# PSFB_gate_driver_sch.net
KiCad netlist of a schematic drawn in Altium Designer
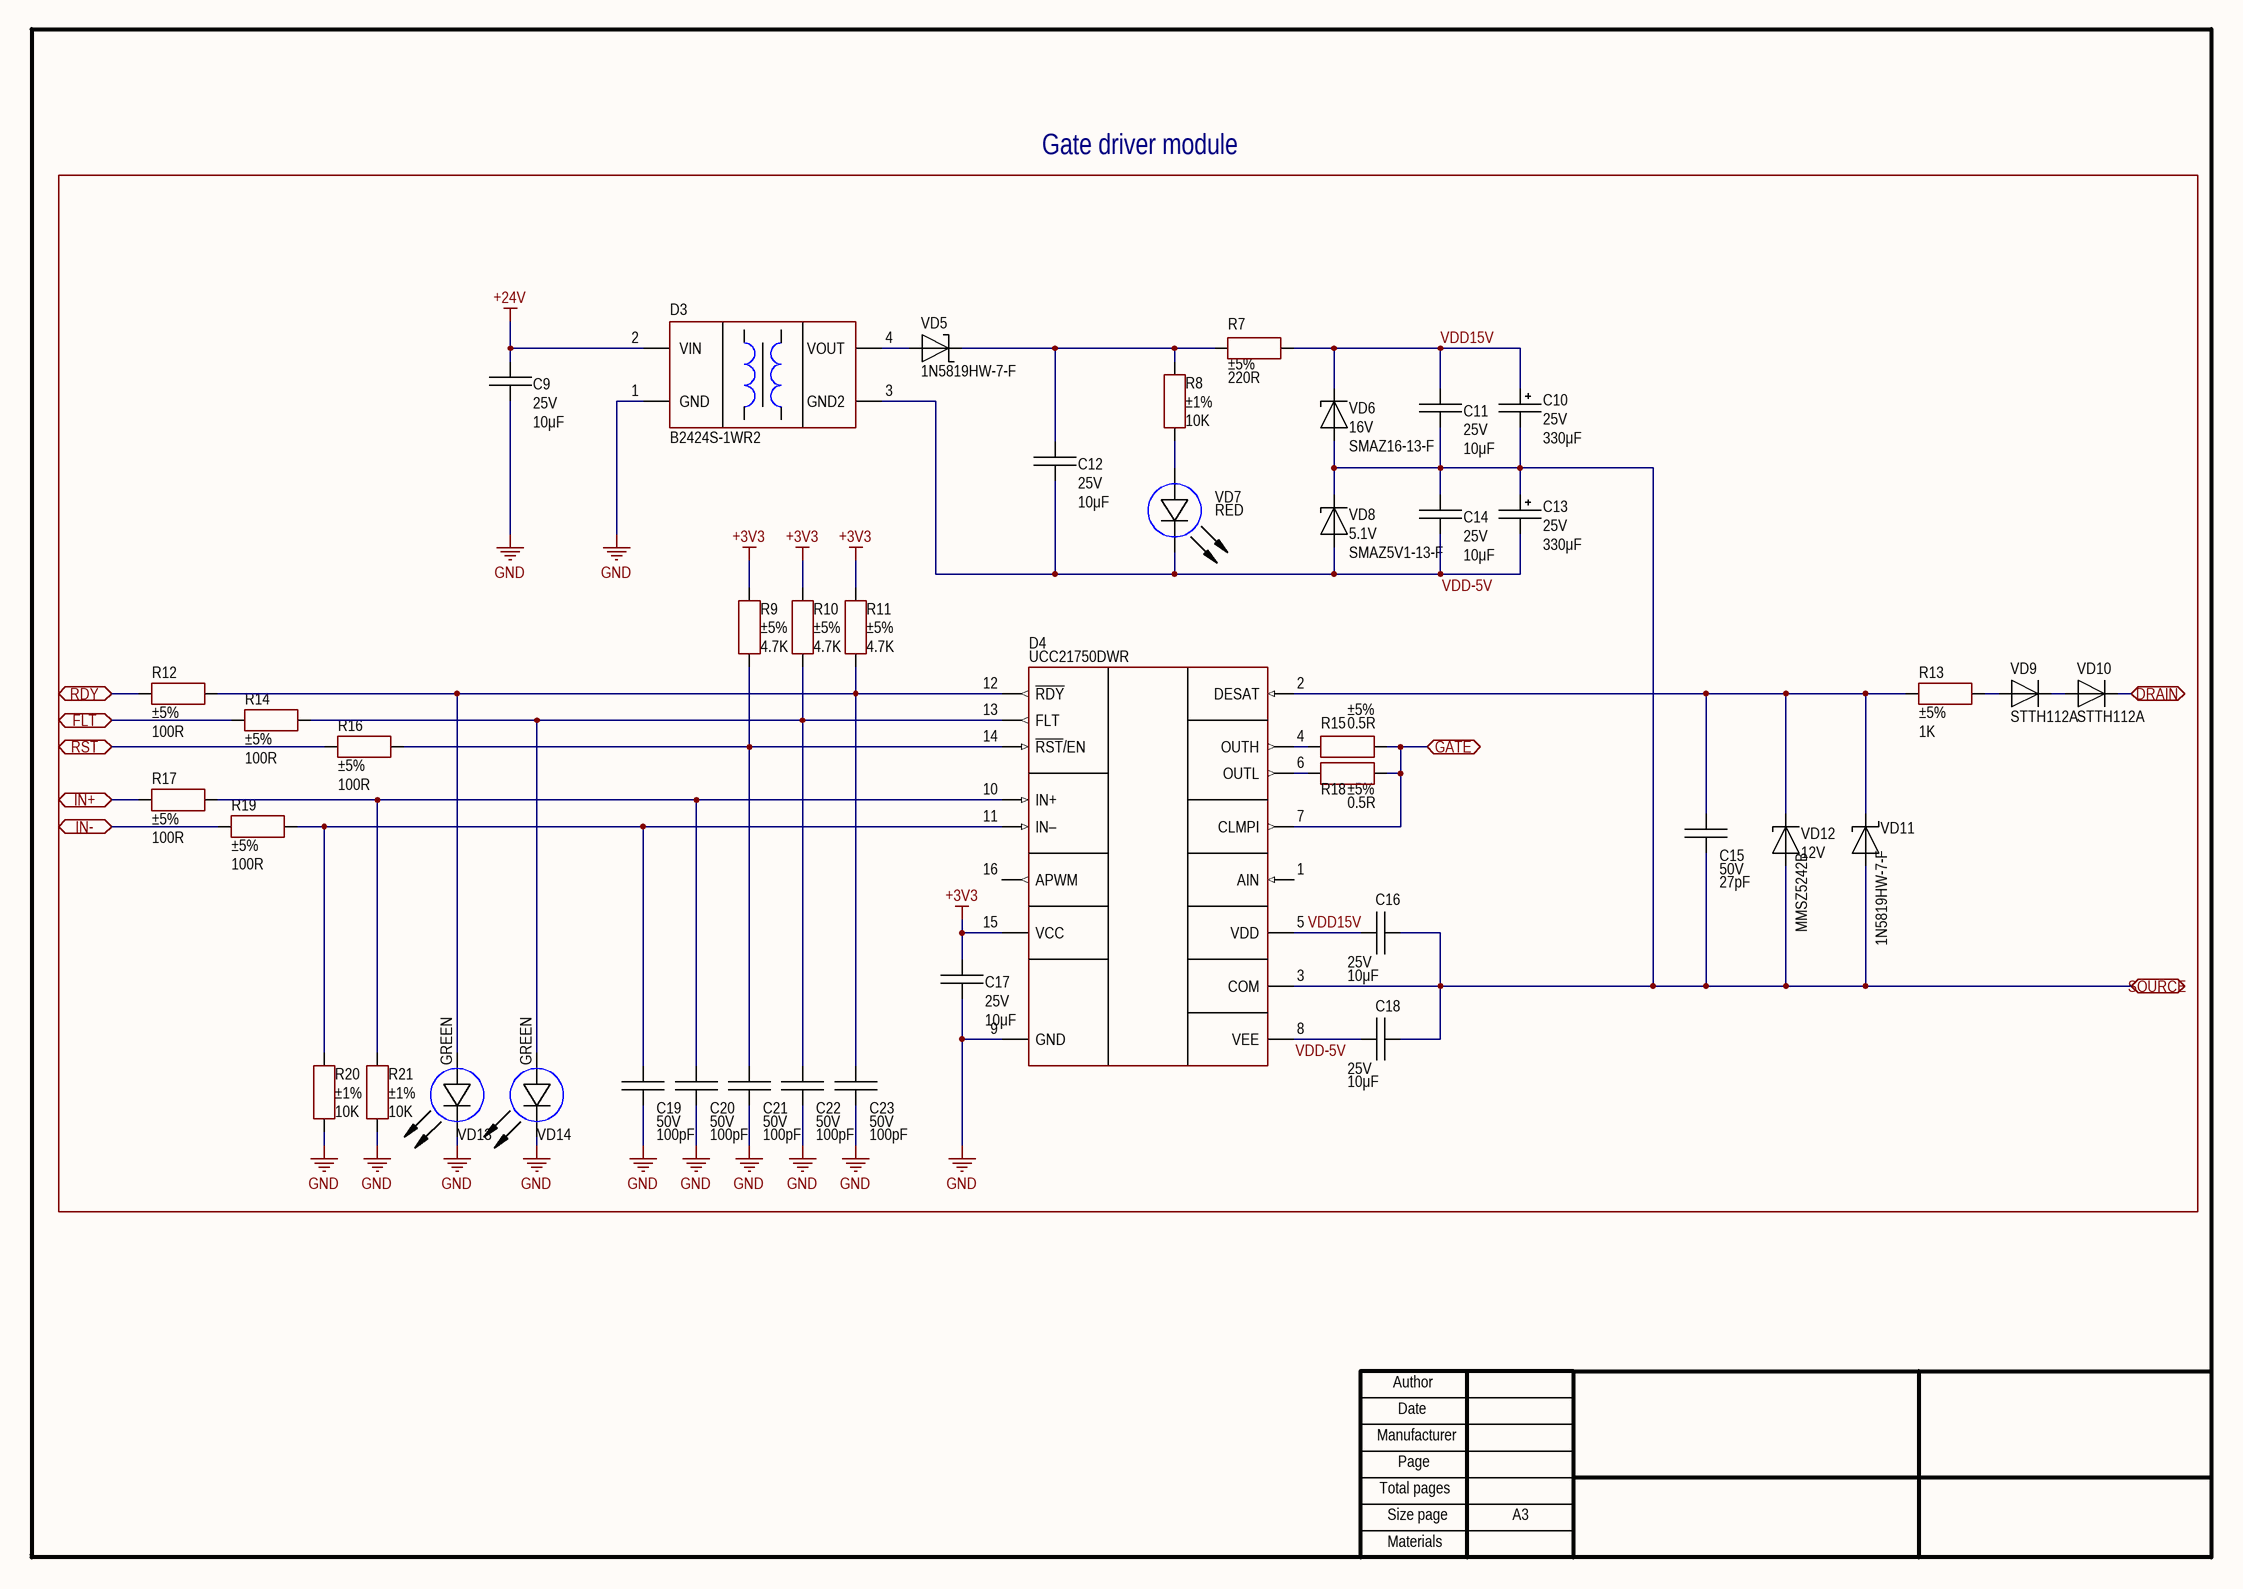
[diagram p0: PSFB_gate_driver_sch.SchDoc]

(export (version "E")
  (design (tool "Eeschema 10.0.6"))
  (components
    (comp (ref "C9")
      (value "10μF")
      (footprint "CAP: 1206")
      (description "10µF ±10% 25V Ceramic Capacitor X7R 1206 (3216 Metric)")
      (fields
        (field (name "MANUFACTURER") "Yageo")
        (field (name "PARTNUMBER") "CC1206KKX7R8BB106")
        (field (name "VOLTAGE") "25V")
      )
      (libsource (lib "capacitor") (part "Ceramic_1206"))
    )
    (comp (ref "C10")
      (value "330μF")
      (footprint "CAP: D8C3.5H12")
      (description "330µF 25V Aluminum - Polymer Capacitors Radial, Can 18mOhm 2000 Hrs @ 105°C")
      (fields
        (field (name "MANUFACTURER") "KEMET")
        (field (name "PARTNUMBER") "A750KS337M1EAAE018")
        (field (name "VOLTAGE") "25V")
      )
      (libsource (lib "capacitor") (part "Aluminium"))
    )
    (comp (ref "C11")
      (value "10μF")
      (footprint "CAP: 1206")
      (description "10µF ±10% 25V Ceramic Capacitor X7R 1206 (3216 Metric)")
      (fields
        (field (name "MANUFACTURER") "Yageo")
        (field (name "PARTNUMBER") "CC1206KKX7R8BB106")
        (field (name "VOLTAGE") "25V")
      )
      (libsource (lib "capacitor") (part "Ceramic_1206"))
    )
    (comp (ref "C12")
      (value "10μF")
      (footprint "CAP: 1206")
      (description "10µF ±10% 25V Ceramic Capacitor X7R 1206 (3216 Metric)")
      (fields
        (field (name "MANUFACTURER") "Yageo")
        (field (name "PARTNUMBER") "CC1206KKX7R8BB106")
        (field (name "VOLTAGE") "25V")
      )
      (libsource (lib "capacitor") (part "Ceramic_1206"))
    )
    (comp (ref "C13")
      (value "330μF")
      (footprint "CAP: D8C3.5H12")
      (description "330µF 25V Aluminum - Polymer Capacitors Radial, Can 18mOhm 2000 Hrs @ 105°C")
      (fields
        (field (name "MANUFACTURER") "KEMET")
        (field (name "PARTNUMBER") "A750KS337M1EAAE018")
        (field (name "VOLTAGE") "25V")
      )
      (libsource (lib "capacitor") (part "Aluminium"))
    )
    (comp (ref "C14")
      (value "10μF")
      (footprint "CAP: 1206")
      (description "10µF ±10% 25V Ceramic Capacitor X7R 1206 (3216 Metric)")
      (fields
        (field (name "MANUFACTURER") "Yageo")
        (field (name "PARTNUMBER") "CC1206KKX7R8BB106")
        (field (name "VOLTAGE") "25V")
      )
      (libsource (lib "capacitor") (part "Ceramic_1206"))
    )
    (comp (ref "C15")
      (value "27pF")
      (footprint "CAP: 0805")
      (description "27pF ±5% 50V Ceramic Capacitor C0G, NP0 0805 (2012 Metric)")
      (fields
        (field (name "MANUFACTURER") "Yageo")
        (field (name "PARTNUMBER") "CC0805JRNPO9BN270")
        (field (name "VOLTAGE") "50V")
      )
      (libsource (lib "capacitor") (part "Ceramic_0805"))
    )
    (comp (ref "C16")
      (value "10μF")
      (footprint "CAP: 1206")
      (description "10µF ±10% 25V Ceramic Capacitor X7R 1206 (3216 Metric)")
      (fields
        (field (name "MANUFACTURER") "Yageo")
        (field (name "PARTNUMBER") "CC1206KKX7R8BB106")
        (field (name "VOLTAGE") "25V")
      )
      (libsource (lib "capacitor") (part "Ceramic_1206"))
    )
    (comp (ref "C17")
      (value "10μF")
      (footprint "CAP: 1206")
      (description "10µF ±10% 25V Ceramic Capacitor X7R 1206 (3216 Metric)")
      (fields
        (field (name "MANUFACTURER") "Yageo")
        (field (name "PARTNUMBER") "CC1206KKX7R8BB106")
        (field (name "VOLTAGE") "25V")
      )
      (libsource (lib "capacitor") (part "Ceramic_1206"))
    )
    (comp (ref "C18")
      (value "10μF")
      (footprint "CAP: 1206")
      (description "10µF ±10% 25V Ceramic Capacitor X7R 1206 (3216 Metric)")
      (fields
        (field (name "MANUFACTURER") "Yageo")
        (field (name "PARTNUMBER") "CC1206KKX7R8BB106")
        (field (name "VOLTAGE") "25V")
      )
      (libsource (lib "capacitor") (part "Ceramic_1206"))
    )
    (comp (ref "C19")
      (value "100pF")
      (footprint "CAP: 0805")
      (description "100pF ±5% 50V Ceramic Capacitor C0G, NP0 0805 (2012 Metric)")
      (fields
        (field (name "MANUFACTURER") "Yageo")
        (field (name "PARTNUMBER") "CC0805JRNPO9BN101")
        (field (name "VOLTAGE") "50V")
      )
      (libsource (lib "capacitor") (part "Ceramic_0805"))
    )
    (comp (ref "C20")
      (value "100pF")
      (footprint "CAP: 0805")
      (description "100pF ±5% 50V Ceramic Capacitor C0G, NP0 0805 (2012 Metric)")
      (fields
        (field (name "MANUFACTURER") "Yageo")
        (field (name "PARTNUMBER") "CC0805JRNPO9BN101")
        (field (name "VOLTAGE") "50V")
      )
      (libsource (lib "capacitor") (part "Ceramic_0805"))
    )
    (comp (ref "C21")
      (value "100pF")
      (footprint "CAP: 0805")
      (description "100pF ±5% 50V Ceramic Capacitor C0G, NP0 0805 (2012 Metric)")
      (fields
        (field (name "MANUFACTURER") "Yageo")
        (field (name "PARTNUMBER") "CC0805JRNPO9BN101")
        (field (name "VOLTAGE") "50V")
      )
      (libsource (lib "capacitor") (part "Ceramic_0805"))
    )
    (comp (ref "C22")
      (value "100pF")
      (footprint "CAP: 0805")
      (description "100pF ±5% 50V Ceramic Capacitor C0G, NP0 0805 (2012 Metric)")
      (fields
        (field (name "MANUFACTURER") "Yageo")
        (field (name "PARTNUMBER") "CC0805JRNPO9BN101")
        (field (name "VOLTAGE") "50V")
      )
      (libsource (lib "capacitor") (part "Ceramic_0805"))
    )
    (comp (ref "C23")
      (value "100pF")
      (footprint "CAP: 0805")
      (description "100pF ±5% 50V Ceramic Capacitor C0G, NP0 0805 (2012 Metric)")
      (fields
        (field (name "MANUFACTURER") "Yageo")
        (field (name "PARTNUMBER") "CC0805JRNPO9BN101")
        (field (name "VOLTAGE") "50V")
      )
      (libsource (lib "capacitor") (part "Ceramic_0805"))
    )
    (comp (ref "D3")
      (value "~")
      (footprint "MOD: SIP-4 (B0505S-1W)")
      (description "Isolated Module DC DC Converter 1 Output 24V 42mA 21.6V - 26.4V Input")
      (fields
        (field (name "MANUFACTURER") "Mornsun")
        (field (name "VALUEMANUFACTURERPARTNUMBER") "DC/DC converter, Isolator, 24V 42mA, -40...+105°C, SIP-4")
        (field (name "PARTNUMBER") "B2424S-1WR2")
      )
      (libsource (lib "module") (part "B0505S-1WR2"))
    )
    (comp (ref "D4")
      (value "~")
      (footprint "16-SOIC")
      (description "10A Gate Driver Capacitive Coupling 5700Vrms 1 Channel 16-SOIC")
      (fields
        (field (name "MANUFACTURER") "Texas Instruments")
        (field (name "VALUEMANUFACTURERPARTNUMBER") "Isolated gate driver, 1200V, , ±10A, 150kV/μs, supply 3...5.5V, -40...+125°C, 16-SOIC")
        (field (name "PARTNUMBER") "UCC21750DWR")
      )
      (libsource (lib "MyLib") (part "UCC21750DWR"))
    )
    (comp (ref "R7")
      (value "220R")
      (footprint "RES: 2512")
      (description "220 Ohms ±5% 1W Chip Resistor 2512 (6432 Metric) Moisture Resistant Thick Film")
      (fields
        (field (name "MANUFACTURER") "Yageo")
        (field (name "PARTNUMBER") "RC2512JK-07220RL")
        (field (name "TOLERANCE") "±5%")
      )
      (libsource (lib "resistor") (part "Resistor_2512"))
    )
    (comp (ref "R8")
      (value "10K")
      (footprint "RES: 0805")
      (description "10 kOhms ±1% 0.125W, 1/8W Chip Resistor 0805 (2012 Metric) Moisture Resistant Thick Film")
      (fields
        (field (name "MANUFACTURER") "Yageo")
        (field (name "PARTNUMBER") "RC0805FR-0710KL")
        (field (name "TOLERANCE") "±1%")
      )
      (libsource (lib "resistor") (part "Resistor_0805"))
    )
    (comp (ref "R9")
      (value "4.7K")
      (footprint "RES: 0805")
      (description "4.7 kOhms ±5% 0.125W, 1/8W Chip Resistor 0805 (2012 Metric) Moisture Resistant Thick Film")
      (fields
        (field (name "MANUFACTURER") "Yageo")
        (field (name "PARTNUMBER") "RC0805JR-074K7L")
        (field (name "TOLERANCE") "±5%")
      )
      (libsource (lib "resistor") (part "Resistor_0805"))
    )
    (comp (ref "R10")
      (value "4.7K")
      (footprint "RES: 0805")
      (description "4.7 kOhms ±5% 0.125W, 1/8W Chip Resistor 0805 (2012 Metric) Moisture Resistant Thick Film")
      (fields
        (field (name "MANUFACTURER") "Yageo")
        (field (name "PARTNUMBER") "RC0805JR-074K7L")
        (field (name "TOLERANCE") "±5%")
      )
      (libsource (lib "resistor") (part "Resistor_0805"))
    )
    (comp (ref "R11")
      (value "4.7K")
      (footprint "RES: 0805")
      (description "4.7 kOhms ±5% 0.125W, 1/8W Chip Resistor 0805 (2012 Metric) Moisture Resistant Thick Film")
      (fields
        (field (name "MANUFACTURER") "Yageo")
        (field (name "PARTNUMBER") "RC0805JR-074K7L")
        (field (name "TOLERANCE") "±5%")
      )
      (libsource (lib "resistor") (part "Resistor_0805"))
    )
    (comp (ref "R12")
      (value "100R")
      (footprint "RES: 0805")
      (description "100 Ohms ±5% 0.125W, 1/8W Chip Resistor 0805 (2012 Metric) Moisture Resistant Thick Film")
      (fields
        (field (name "MANUFACTURER") "Yageo")
        (field (name "PARTNUMBER") "RC0805JR-07100RL")
        (field (name "TOLERANCE") "±5%")
      )
      (libsource (lib "") (part "Resistor_0805_1"))
    )
    (comp (ref "R13")
      (value "1K")
      (footprint "RES: 0805")
      (description "1 kOhms ±5% 0.125W, 1/8W Chip Resistor 0805 (2012 Metric) Moisture Resistant Thick Film")
      (fields
        (field (name "MANUFACTURER") "Yageo")
        (field (name "PARTNUMBER") "RC0805JR-071KL")
        (field (name "TOLERANCE") "±5%")
      )
      (libsource (lib "") (part "Resistor_0805_1"))
    )
    (comp (ref "R14")
      (value "100R")
      (footprint "RES: 0805")
      (description "100 Ohms ±5% 0.125W, 1/8W Chip Resistor 0805 (2012 Metric) Moisture Resistant Thick Film")
      (fields
        (field (name "MANUFACTURER") "Yageo")
        (field (name "PARTNUMBER") "RC0805JR-07100RL")
        (field (name "TOLERANCE") "±5%")
      )
      (libsource (lib "") (part "Resistor_0805_1"))
    )
    (comp (ref "R15")
      (value "0.5R")
      (footprint "RES: 2512")
      (fields
        (field (name "MANUFACTURER") "Yageo")
        (field (name "PARTNUMBER") "RC2512JK-07100RL")
        (field (name "VALUEMANUFACTURERPARTNUMBER") "Resistor film, 0.5R, ±5%, 2512, 1W, -55...+125°C")
        (field (name "TOLERANCE") "±5%")
      )
      (libsource (lib "resistor") (part "Resistor_2512"))
    )
    (comp (ref "R16")
      (value "100R")
      (footprint "RES: 0805")
      (description "100 Ohms ±5% 0.125W, 1/8W Chip Resistor 0805 (2012 Metric) Moisture Resistant Thick Film")
      (fields
        (field (name "MANUFACTURER") "Yageo")
        (field (name "PARTNUMBER") "RC0805JR-07100RL")
        (field (name "TOLERANCE") "±5%")
      )
      (libsource (lib "") (part "Resistor_0805_1"))
    )
    (comp (ref "R17")
      (value "100R")
      (footprint "RES: 0805")
      (description "100 Ohms ±5% 0.125W, 1/8W Chip Resistor 0805 (2012 Metric) Moisture Resistant Thick Film")
      (fields
        (field (name "MANUFACTURER") "Yageo")
        (field (name "PARTNUMBER") "RC0805JR-07100RL")
        (field (name "TOLERANCE") "±5%")
      )
      (libsource (lib "") (part "Resistor_0805_1"))
    )
    (comp (ref "R18")
      (value "0.5R")
      (footprint "RES: 2512")
      (fields
        (field (name "MANUFACTURER") "Yageo")
        (field (name "PARTNUMBER") "RC2512JK-07100RL")
        (field (name "VALUEMANUFACTURERPARTNUMBER") "Resistor film, 0.5R, ±5%, 2512, 1W, -55...+125°C")
        (field (name "TOLERANCE") "±5%")
      )
      (libsource (lib "resistor") (part "Resistor_2512"))
    )
    (comp (ref "R19")
      (value "100R")
      (footprint "RES: 0805")
      (description "100 Ohms ±5% 0.125W, 1/8W Chip Resistor 0805 (2012 Metric) Moisture Resistant Thick Film")
      (fields
        (field (name "MANUFACTURER") "Yageo")
        (field (name "PARTNUMBER") "RC0805JR-07100RL")
        (field (name "TOLERANCE") "±5%")
      )
      (libsource (lib "") (part "Resistor_0805_1"))
    )
    (comp (ref "R20")
      (value "10K")
      (footprint "RES: 0805")
      (description "10 kOhms ±1% 0.125W, 1/8W Chip Resistor 0805 (2012 Metric) Moisture Resistant Thick Film")
      (fields
        (field (name "MANUFACTURER") "Yageo")
        (field (name "PARTNUMBER") "RC0805FR-0710KL")
        (field (name "TOLERANCE") "±1%")
      )
      (libsource (lib "") (part "Resistor_0805_2"))
    )
    (comp (ref "R21")
      (value "10K")
      (footprint "RES: 0805")
      (description "10 kOhms ±1% 0.125W, 1/8W Chip Resistor 0805 (2012 Metric) Moisture Resistant Thick Film")
      (fields
        (field (name "MANUFACTURER") "Yageo")
        (field (name "PARTNUMBER") "RC0805FR-0710KL")
        (field (name "TOLERANCE") "±1%")
      )
      (libsource (lib "") (part "Resistor_0805_2"))
    )
    (comp (ref "VD5")
      (value "~")
      (footprint "DIODE: SOD123")
      (description "Diode Schottky 40V 1A Surface Mount SOD-123C")
      (fields
        (field (name "MANUFACTURER") "Diodes Incorporated")
        (field (name "VALUEMANUFACTURERPARTNUMBER") "Schottky diode, 40V, 1A, 0.45V, 15pF, SOD-123, -55...+150°C")
        (field (name "PARTNUMBER") "1N5819HW-7-F")
      )
      (libsource (lib "diode") (part "Schottky_single"))
    )
    (comp (ref "VD6")
      (value "~")
      (footprint "DIODE: SMA")
      (description "Zener Diode 16V 1W ±5% Surface Mount SMA")
      (fields
        (field (name "MANUFACTURER") "Diodes Incorporated")
        (field (name "VALUEMANUFACTURERPARTNUMBER") "Zener diode, 16V, 1W, 0.9V, 17Ohm, SMA, -55...+150°C")
        (field (name "VOLTAGE") "16V")
        (field (name "PARTNUMBER") "SMAZ16-13-F")
      )
      (libsource (lib "diode") (part "Zener_single"))
    )
    (comp (ref "VD7")
      (value "~")
      (footprint "LED: 0805R")
      (description "Red 631nm LED Indication - Discrete 2V 0805 (2012 Metric)")
      (fields
        (field (name "MANUFACTURER") "Lite-On Inc.")
        (field (name "VALUEMANUFACTURERPARTNUMBER") "LED, Red, 20mA, 2V, 0805, -55...+150°C")
        (field (name "COLOR") "RED")
      )
      (libsource (lib "diode") (part "LED_single"))
    )
    (comp (ref "VD8")
      (value "~")
      (footprint "DIODE: SMA")
      (description "Zener Diode 5.1V 1W ±5% Surface Mount SMA")
      (fields
        (field (name "MANUFACTURER") "Diodes Incorporated")
        (field (name "VALUEMANUFACTURERPARTNUMBER") "Zener diode, 5.1V, 1W, 0.9V, 17Ohm, SMA, -55...+150°C")
        (field (name "VOLTAGE") "5.1V")
        (field (name "PARTNUMBER") "SMAZ5V1-13-F")
      )
      (libsource (lib "diode") (part "Zener_single"))
    )
    (comp (ref "VD9")
      (value "~")
      (footprint "DIODE: SMA")
      (description "Diode Standard 1200V 1A Surface Mount SMA")
      (fields
        (field (name "MANUFACTURER") "STMicroelectronics")
        (field (name "VALUEMANUFACTURERPARTNUMBER") "Single diode, 1200V, 1A, 1.9V, 75ns, SMA, -55...+150°C")
        (field (name "PARTNUMBER") "STTH112A")
      )
      (libsource (lib "diode") (part "Diode_single"))
    )
    (comp (ref "VD10")
      (value "~")
      (footprint "DIODE: SMA")
      (description "Diode Standard 1200V 1A Surface Mount SMA")
      (fields
        (field (name "MANUFACTURER") "STMicroelectronics")
        (field (name "VALUEMANUFACTURERPARTNUMBER") "Single diode, 1200V, 1A, 1.9V, 75ns, SMA, -55...+150°C")
        (field (name "PARTNUMBER") "STTH112A")
      )
      (libsource (lib "diode") (part "Diode_single"))
    )
    (comp (ref "VD11")
      (value "~")
      (footprint "DIODE: SOD123")
      (description "Diode Schottky 40V 1A Surface Mount SOD-123C")
      (fields
        (field (name "MANUFACTURER") "Diodes Incorporated")
        (field (name "VALUEMANUFACTURERPARTNUMBER") "Schottky diode, 40V, 1A, 0.45V, 15pF, SOD-123, -55...+150°C")
        (field (name "PARTNUMBER") "1N5819HW-7-F")
      )
      (libsource (lib "diode") (part "Schottky_single"))
    )
    (comp (ref "VD12")
      (value "~")
      (footprint "DIODE: SOD123")
      (description "Zener Diode 12V 500mW ±5% Surface Mount SOD-123")
      (fields
        (field (name "MANUFACTURER") "Diodes Incorporated")
        (field (name "VALUEMANUFACTURERPARTNUMBER") "Zener diode, 12V, 500mW, 0.9V, 17Ohm, SOD-123, -55...+150°C")
        (field (name "VOLTAGE") "12V")
        (field (name "PARTNUMBER") "MMSZ5242B")
      )
      (libsource (lib "diode") (part "Zener_single"))
    )
    (comp (ref "VD13")
      (value "~")
      (footprint "LED: 0805G")
      (description "Green 571nm LED Indication - Discrete 2V 0805 (2012 Metric)")
      (fields
        (field (name "MANUFACTURER") "Lite-On Inc.")
        (field (name "VALUEMANUFACTURERPARTNUMBER") "LED, Green, 20mA, 2V, 0805, -55...+150°C")
        (field (name "COLOR") "GREEN")
      )
      (libsource (lib "diode") (part "LED_single"))
    )
    (comp (ref "VD14")
      (value "~")
      (footprint "LED: 0805G")
      (description "Green 571nm LED Indication - Discrete 2V 0805 (2012 Metric)")
      (fields
        (field (name "MANUFACTURER") "Lite-On Inc.")
        (field (name "VALUEMANUFACTURERPARTNUMBER") "LED, Green, 20mA, 2V, 0805, -55...+150°C")
        (field (name "COLOR") "GREEN")
      )
      (libsource (lib "diode") (part "LED_single"))
    )
  )
  (nets
    (net (code "1") (name "+3V3") (class "Default")
      (node (ref "C17") (pin "2") (pinfunction "2_2") (pintype "passive"))
      (node (ref "D4") (pin "15") (pinfunction "VCC_15") (pintype "power_in"))
      (node (ref "R10") (pin "2") (pinfunction "2_2") (pintype "passive"))
      (node (ref "R11") (pin "2") (pinfunction "2_2") (pintype "passive"))
      (node (ref "R9") (pin "2") (pinfunction "2_2") (pintype "passive"))
    )
    (net (code "2") (name "+24V") (class "Default")
      (node (ref "C9") (pin "2") (pinfunction "2_2") (pintype "passive"))
      (node (ref "D3") (pin "2") (pinfunction "VIN_2") (pintype "power_in"))
    )
    (net (code "3") (name "/DRAIN") (class "Default")
      (node (ref "VD10") (pin "2") (pinfunction "2_2") (pintype "passive"))
    )
    (net (code "4") (name "/FLT") (class "Default")
      (node (ref "R14") (pin "1") (pinfunction "1_1") (pintype "passive"))
    )
    (net (code "5") (name "/GATE") (class "Default")
      (node (ref "D4") (pin "7") (pinfunction "CLMPI_7") (pintype "output"))
      (node (ref "R15") (pin "2") (pinfunction "2_2") (pintype "passive"))
      (node (ref "R18") (pin "2") (pinfunction "2_2") (pintype "passive"))
    )
    (net (code "6") (name "/IN+") (class "Default")
      (node (ref "R17") (pin "1") (pinfunction "1_1") (pintype "passive"))
    )
    (net (code "7") (name "/IN-") (class "Default")
      (node (ref "R19") (pin "1") (pinfunction "1_1") (pintype "passive"))
    )
    (net (code "8") (name "/RDY") (class "Default")
      (node (ref "R12") (pin "1") (pinfunction "1_1") (pintype "passive"))
    )
    (net (code "9") (name "/RST") (class "Default")
      (node (ref "R16") (pin "1") (pinfunction "1_1") (pintype "passive"))
    )
    (net (code "10") (name "/SOURCE") (class "Default")
      (node (ref "C10") (pin "2") (pinfunction "2_2") (pintype "passive"))
      (node (ref "C11") (pin "2") (pinfunction "2_2") (pintype "passive"))
      (node (ref "C13") (pin "1") (pinfunction "1_1") (pintype "passive"))
      (node (ref "C14") (pin "1") (pinfunction "1_1") (pintype "passive"))
      (node (ref "C15") (pin "1") (pinfunction "1_1") (pintype "passive"))
      (node (ref "C16") (pin "1") (pinfunction "1_1") (pintype "passive"))
      (node (ref "C18") (pin "1") (pinfunction "1_1") (pintype "passive"))
      (node (ref "D4") (pin "3") (pinfunction "COM_3") (pintype "power_in"))
      (node (ref "VD11") (pin "1") (pinfunction "1_1") (pintype "passive"))
      (node (ref "VD12") (pin "1") (pinfunction "A_1") (pintype "passive"))
      (node (ref "VD6") (pin "1") (pinfunction "A_1") (pintype "passive"))
      (node (ref "VD8") (pin "2") (pinfunction "C_2") (pintype "passive"))
    )
    (net (code "11") (name "/VDD-5V") (class "Default")
      (node (ref "C12") (pin "1") (pinfunction "1_1") (pintype "passive"))
      (node (ref "C13") (pin "2") (pinfunction "2_2") (pintype "passive"))
      (node (ref "C14") (pin "2") (pinfunction "2_2") (pintype "passive"))
      (node (ref "C18") (pin "2") (pinfunction "2_2") (pintype "passive"))
      (node (ref "D3") (pin "3") (pinfunction "GND2_3") (pintype "power_in"))
      (node (ref "D4") (pin "8") (pinfunction "VEE_8") (pintype "power_in"))
      (node (ref "VD7") (pin "2") (pinfunction "C_2") (pintype "passive"))
      (node (ref "VD8") (pin "1") (pinfunction "A_1") (pintype "passive"))
    )
    (net (code "12") (name "/VDD15V") (class "Default")
      (node (ref "C10") (pin "1") (pinfunction "1_1") (pintype "passive"))
      (node (ref "C11") (pin "1") (pinfunction "1_1") (pintype "passive"))
      (node (ref "C16") (pin "2") (pinfunction "2_2") (pintype "passive"))
      (node (ref "D4") (pin "5") (pinfunction "VDD_5") (pintype "power_in"))
      (node (ref "R7") (pin "2") (pinfunction "2_2") (pintype "passive"))
      (node (ref "VD6") (pin "2") (pinfunction "C_2") (pintype "passive"))
    )
    (net (code "13") (name "GND") (class "Default")
      (node (ref "C17") (pin "1") (pinfunction "1_1") (pintype "passive"))
      (node (ref "C19") (pin "1") (pinfunction "1_1") (pintype "passive"))
      (node (ref "C20") (pin "1") (pinfunction "1_1") (pintype "passive"))
      (node (ref "C21") (pin "1") (pinfunction "1_1") (pintype "passive"))
      (node (ref "C22") (pin "1") (pinfunction "1_1") (pintype "passive"))
      (node (ref "C23") (pin "1") (pinfunction "1_1") (pintype "passive"))
      (node (ref "C9") (pin "1") (pinfunction "1_1") (pintype "passive"))
      (node (ref "D3") (pin "1") (pinfunction "GND_1") (pintype "power_in"))
      (node (ref "D4") (pin "9") (pinfunction "GND_9") (pintype "power_in"))
      (node (ref "R20") (pin "2") (pinfunction "2_2") (pintype "passive"))
      (node (ref "R21") (pin "2") (pinfunction "2_2") (pintype "passive"))
      (node (ref "VD13") (pin "2") (pinfunction "C_2") (pintype "passive"))
      (node (ref "VD14") (pin "2") (pinfunction "C_2") (pintype "passive"))
    )
    (net (code "14") (name "Net-(C12-Pad2)") (class "Default")
      (node (ref "C12") (pin "2") (pinfunction "2_2") (pintype "passive"))
      (node (ref "R7") (pin "1") (pinfunction "1_1") (pintype "passive"))
      (node (ref "R8") (pin "2") (pinfunction "2_2") (pintype "passive"))
      (node (ref "VD5") (pin "2") (pinfunction "2_2") (pintype "passive"))
    )
    (net (code "15") (name "Net-(D3-VOUT)") (class "Default")
      (node (ref "D3") (pin "4") (pinfunction "VOUT_4") (pintype "power_in"))
      (node (ref "VD5") (pin "1") (pinfunction "1_1") (pintype "passive"))
    )
    (net (code "16") (name "Net-(D4-DESAT)") (class "Default")
      (node (ref "C15") (pin "2") (pinfunction "2_2") (pintype "passive"))
      (node (ref "D4") (pin "2") (pinfunction "DESAT_2") (pintype "input"))
      (node (ref "R13") (pin "1") (pinfunction "1_1") (pintype "passive"))
      (node (ref "VD11") (pin "2") (pinfunction "2_2") (pintype "passive"))
      (node (ref "VD12") (pin "2") (pinfunction "C_2") (pintype "passive"))
    )
    (net (code "17") (name "Net-(D4-FLT)") (class "Default")
      (node (ref "C22") (pin "2") (pinfunction "2_2") (pintype "passive"))
      (node (ref "D4") (pin "13") (pinfunction "FLT_13") (pintype "output"))
      (node (ref "R10") (pin "1") (pinfunction "1_1") (pintype "passive"))
      (node (ref "R14") (pin "2") (pinfunction "2_2") (pintype "passive"))
      (node (ref "VD14") (pin "1") (pinfunction "A_1") (pintype "passive"))
    )
    (net (code "18") (name "Net-(D4-IN+)") (class "Default")
      (node (ref "C20") (pin "2") (pinfunction "2_2") (pintype "passive"))
      (node (ref "D4") (pin "10") (pinfunction "IN+_10") (pintype "input"))
      (node (ref "R17") (pin "2") (pinfunction "2_2") (pintype "passive"))
      (node (ref "R21") (pin "1") (pinfunction "1_1") (pintype "passive"))
    )
    (net (code "19") (name "Net-(D4-IN–)") (class "Default")
      (node (ref "C19") (pin "2") (pinfunction "2_2") (pintype "passive"))
      (node (ref "D4") (pin "11") (pinfunction "IN–_11") (pintype "input"))
      (node (ref "R19") (pin "2") (pinfunction "2_2") (pintype "passive"))
      (node (ref "R20") (pin "1") (pinfunction "1_1") (pintype "passive"))
    )
    (net (code "20") (name "Net-(D4-OUTH)") (class "Default")
      (node (ref "D4") (pin "4") (pinfunction "OUTH_4") (pintype "output"))
      (node (ref "R15") (pin "1") (pinfunction "1_1") (pintype "passive"))
    )
    (net (code "21") (name "Net-(D4-OUTL)") (class "Default")
      (node (ref "D4") (pin "6") (pinfunction "OUTL_6") (pintype "output"))
      (node (ref "R18") (pin "1") (pinfunction "1_1") (pintype "passive"))
    )
    (net (code "22") (name "Net-(D4-~{RDY})") (class "Default")
      (node (ref "C23") (pin "2") (pinfunction "2_2") (pintype "passive"))
      (node (ref "D4") (pin "12") (pinfunction "~{RDY}_12") (pintype "output"))
      (node (ref "R11") (pin "1") (pinfunction "1_1") (pintype "passive"))
      (node (ref "R12") (pin "2") (pinfunction "2_2") (pintype "passive"))
      (node (ref "VD13") (pin "1") (pinfunction "A_1") (pintype "passive"))
    )
    (net (code "23") (name "Net-(D4-~{RST}{slash}EN)") (class "Default")
      (node (ref "C21") (pin "2") (pinfunction "2_2") (pintype "passive"))
      (node (ref "D4") (pin "14") (pinfunction "~{RST}/EN_14") (pintype "input"))
      (node (ref "R16") (pin "2") (pinfunction "2_2") (pintype "passive"))
      (node (ref "R9") (pin "1") (pinfunction "1_1") (pintype "passive"))
    )
    (net (code "24") (name "Net-(R13-Pad2)") (class "Default")
      (node (ref "R13") (pin "2") (pinfunction "2_2") (pintype "passive"))
      (node (ref "VD9") (pin "1") (pinfunction "1_1") (pintype "passive"))
    )
    (net (code "25") (name "Net-(VD7-A)") (class "Default")
      (node (ref "R8") (pin "1") (pinfunction "1_1") (pintype "passive"))
      (node (ref "VD7") (pin "1") (pinfunction "A_1") (pintype "passive"))
    )
    (net (code "26") (name "Net-(VD10-Pad1)") (class "Default")
      (node (ref "VD10") (pin "1") (pinfunction "1_1") (pintype "passive"))
      (node (ref "VD9") (pin "2") (pinfunction "2_2") (pintype "passive"))
    )
    (net (code "27") (name "unconnected-(D4-AIN-Pad1)") (class "Default")
      (node (ref "D4") (pin "1") (pinfunction "AIN_1") (pintype "input"))
    )
    (net (code "28") (name "unconnected-(D4-APWM-Pad16)") (class "Default")
      (node (ref "D4") (pin "16") (pinfunction "APWM_16") (pintype "output"))
    )
  )
)
